# boot_cfg.net
KiCad netlist of a schematic drawn in Altium Designer
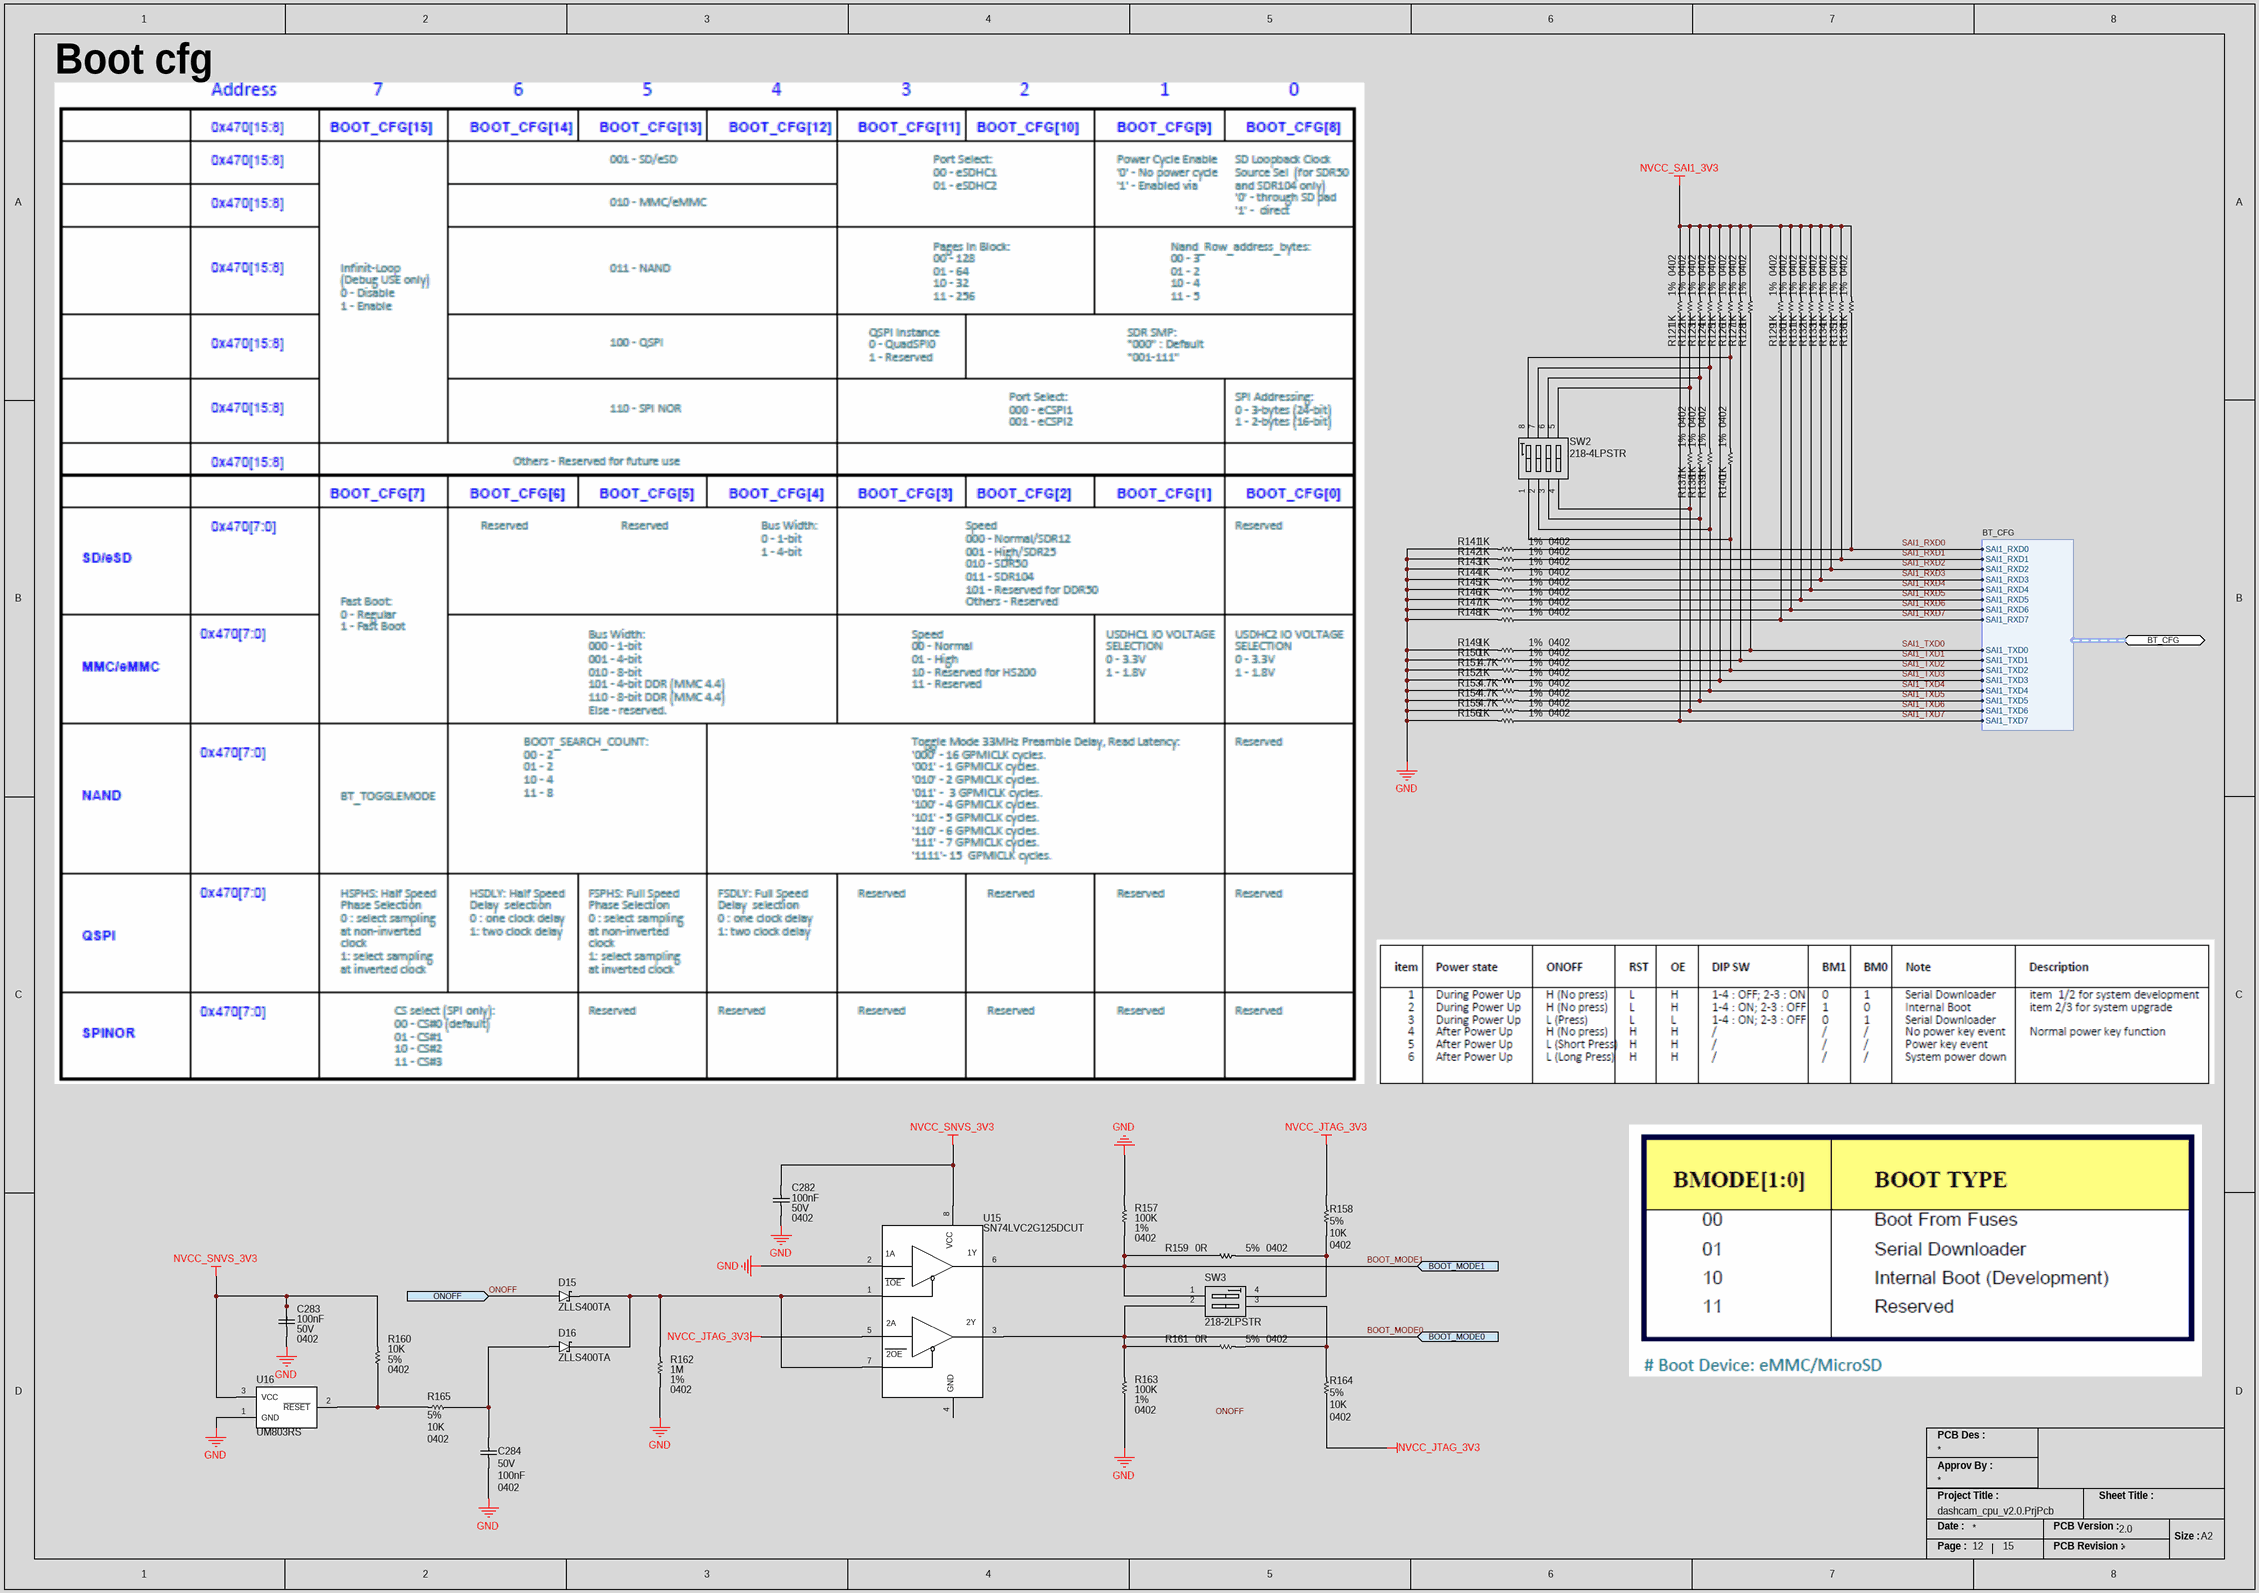
[diagram p0: boot_cfg.SchDoc]

(export (version "E")
  (design (tool "Eeschema 10.0.6"))
  (components
    (comp (ref "C282")
      (value "GRM155R71H104KE14D")
      (footprint "CAP_0402_CAPC1005X05N")
      (description "Multilayer Ceramic Capacitor, 0.1 uF, 16 V, ± 10%, X7R, 0402 [1005 Metric]")
      (fields
        (field (name "MANUFACTURER") "Murata")
        (field (name "TOLERANCE") "10%")
        (field (name "VOLTAGE RATING") "50V")
        (field (name "CAPACITANCE") "100nF")
        (field (name "CASE/PACKAGE") "0402")
      )
      (libsource (lib "Electronic Devices_LIB") (part "CAP_100NF_50V_X7R_0402"))
    )
    (comp (ref "C283")
      (value "GRM155R71H104KE14D")
      (footprint "CAP_0402_CAPC1005X05N")
      (description "Multilayer Ceramic Capacitor, 0.1 uF, 16 V, ± 10%, X7R, 0402 [1005 Metric]")
      (fields
        (field (name "MANUFACTURER") "Murata")
        (field (name "TOLERANCE") "10%")
        (field (name "VOLTAGE RATING") "50V")
        (field (name "CAPACITANCE") "100nF")
        (field (name "CASE/PACKAGE") "0402")
      )
      (libsource (lib "Electronic Devices_LIB") (part "CAP_100NF_50V_X7R_0402"))
    )
    (comp (ref "C284")
      (value "GRM155R71H104KE14D")
      (footprint "CAP_0402_CAPC1005X05N")
      (description "Multilayer Ceramic Capacitor, 0.1 uF, 16 V, ± 10%, X7R, 0402 [1005 Metric]")
      (fields
        (field (name "MANUFACTURER") "Murata")
        (field (name "TOLERANCE") "10%")
        (field (name "VOLTAGE RATING") "50V")
        (field (name "CAPACITANCE") "100nF")
        (field (name "CASE/PACKAGE") "0402")
      )
      (libsource (lib "Electronic Devices_LIB") (part "CAP_100NF_50V_X7R_0402"))
    )
    (comp (ref "D15")
      (value "ZLLS400TA")
      (footprint "DIO_SOD2512X113N")
      (description "DIODE SCHOTTKY 40V 520MA SOD323")
      (fields (field (name "MANUFACTURER") "Diodes Zetex"))
      (libsource (lib "Electronic Devices_LIB") (part "DIO_SCTKY_40V_520mA_ZLLS400TA"))
    )
    (comp (ref "D16")
      (value "ZLLS400TA")
      (footprint "DIO_SOD2512X113N")
      (description "DIODE SCHOTTKY 40V 520MA SOD323")
      (fields (field (name "MANUFACTURER") "Diodes Zetex"))
      (libsource (lib "Electronic Devices_LIB") (part "DIO_SCTKY_40V_520mA_ZLLS400TA"))
    )
    (comp (ref "R121")
      (value "ERJ-2RKF1001X")
      (footprint "RES_0402_RESC1005X04N")
      (description "RES SMD 1K OHM 1% 1/10W 0402")
      (fields
        (field (name "MANUFACTURER") "Panasonic")
        (field (name "RESISTANCE") "1K")
        (field (name "TOLERANCE") "1%")
        (field (name "CASE/PACKAGE") "0402")
      )
      (libsource (lib "Electronic Devices_LIB") (part "RES_1K_1%_100mW_0402"))
    )
    (comp (ref "R122")
      (value "ERJ-2RKF1001X")
      (footprint "RES_0402_RESC1005X04N")
      (description "RES SMD 1K OHM 1% 1/10W 0402")
      (fields
        (field (name "MANUFACTURER") "Panasonic")
        (field (name "RESISTANCE") "1K")
        (field (name "TOLERANCE") "1%")
        (field (name "CASE/PACKAGE") "0402")
      )
      (libsource (lib "Electronic Devices_LIB") (part "RES_1K_1%_100mW_0402"))
    )
    (comp (ref "R123")
      (value "ERJ-2RKF1001X")
      (footprint "RES_0402_RESC1005X04N")
      (description "RES SMD 1K OHM 1% 1/10W 0402")
      (fields
        (field (name "MANUFACTURER") "Panasonic")
        (field (name "RESISTANCE") "1K")
        (field (name "TOLERANCE") "1%")
        (field (name "CASE/PACKAGE") "0402")
      )
      (libsource (lib "Electronic Devices_LIB") (part "RES_1K_1%_100mW_0402"))
    )
    (comp (ref "R124")
      (value "ERJ-2RKF1001X")
      (footprint "RES_0402_RESC1005X04N")
      (description "RES SMD 1K OHM 1% 1/10W 0402")
      (fields
        (field (name "MANUFACTURER") "Panasonic")
        (field (name "RESISTANCE") "1K")
        (field (name "TOLERANCE") "1%")
        (field (name "CASE/PACKAGE") "0402")
      )
      (libsource (lib "Electronic Devices_LIB") (part "RES_1K_1%_100mW_0402"))
    )
    (comp (ref "R125")
      (value "ERJ-2RKF1001X")
      (footprint "RES_0402_RESC1005X04N")
      (description "RES SMD 1K OHM 1% 1/10W 0402")
      (fields
        (field (name "MANUFACTURER") "Panasonic")
        (field (name "RESISTANCE") "1K")
        (field (name "TOLERANCE") "1%")
        (field (name "CASE/PACKAGE") "0402")
      )
      (libsource (lib "Electronic Devices_LIB") (part "RES_1K_1%_100mW_0402"))
    )
    (comp (ref "R126")
      (value "ERJ-2RKF1001X")
      (footprint "RES_0402_RESC1005X04N")
      (description "RES SMD 1K OHM 1% 1/10W 0402")
      (fields
        (field (name "MANUFACTURER") "Panasonic")
        (field (name "RESISTANCE") "1K")
        (field (name "TOLERANCE") "1%")
        (field (name "CASE/PACKAGE") "0402")
      )
      (libsource (lib "Electronic Devices_LIB") (part "RES_1K_1%_100mW_0402"))
    )
    (comp (ref "R127")
      (value "ERJ-2RKF1001X")
      (footprint "RES_0402_RESC1005X04N")
      (description "RES SMD 1K OHM 1% 1/10W 0402")
      (fields
        (field (name "MANUFACTURER") "Panasonic")
        (field (name "RESISTANCE") "1K")
        (field (name "TOLERANCE") "1%")
        (field (name "CASE/PACKAGE") "0402")
      )
      (libsource (lib "Electronic Devices_LIB") (part "RES_1K_1%_100mW_0402"))
    )
    (comp (ref "R128")
      (value "ERJ-2RKF1001X")
      (footprint "RES_0402_RESC1005X04N")
      (description "RES SMD 1K OHM 1% 1/10W 0402")
      (fields
        (field (name "MANUFACTURER") "Panasonic")
        (field (name "RESISTANCE") "1K")
        (field (name "TOLERANCE") "1%")
        (field (name "CASE/PACKAGE") "0402")
      )
      (libsource (lib "Electronic Devices_LIB") (part "RES_1K_1%_100mW_0402"))
    )
    (comp (ref "R129")
      (value "ERJ-2RKF1001X")
      (footprint "RES_0402_RESC1005X04N")
      (description "RES SMD 1K OHM 1% 1/10W 0402")
      (fields
        (field (name "MANUFACTURER") "Panasonic")
        (field (name "RESISTANCE") "1K")
        (field (name "TOLERANCE") "1%")
        (field (name "CASE/PACKAGE") "0402")
      )
      (libsource (lib "Electronic Devices_LIB") (part "RES_1K_1%_100mW_0402"))
    )
    (comp (ref "R130")
      (value "ERJ-2RKF1001X")
      (footprint "RES_0402_RESC1005X04N")
      (description "RES SMD 1K OHM 1% 1/10W 0402")
      (fields
        (field (name "MANUFACTURER") "Panasonic")
        (field (name "RESISTANCE") "1K")
        (field (name "TOLERANCE") "1%")
        (field (name "CASE/PACKAGE") "0402")
      )
      (libsource (lib "Electronic Devices_LIB") (part "RES_1K_1%_100mW_0402"))
    )
    (comp (ref "R131")
      (value "ERJ-2RKF1001X")
      (footprint "RES_0402_RESC1005X04N")
      (description "RES SMD 1K OHM 1% 1/10W 0402")
      (fields
        (field (name "MANUFACTURER") "Panasonic")
        (field (name "RESISTANCE") "1K")
        (field (name "TOLERANCE") "1%")
        (field (name "CASE/PACKAGE") "0402")
      )
      (libsource (lib "Electronic Devices_LIB") (part "RES_1K_1%_100mW_0402"))
    )
    (comp (ref "R132")
      (value "ERJ-2RKF1001X")
      (footprint "RES_0402_RESC1005X04N")
      (description "RES SMD 1K OHM 1% 1/10W 0402")
      (fields
        (field (name "MANUFACTURER") "Panasonic")
        (field (name "RESISTANCE") "1K")
        (field (name "TOLERANCE") "1%")
        (field (name "CASE/PACKAGE") "0402")
      )
      (libsource (lib "Electronic Devices_LIB") (part "RES_1K_1%_100mW_0402"))
    )
    (comp (ref "R133")
      (value "ERJ-2RKF1001X")
      (footprint "RES_0402_RESC1005X04N")
      (description "RES SMD 1K OHM 1% 1/10W 0402")
      (fields
        (field (name "MANUFACTURER") "Panasonic")
        (field (name "RESISTANCE") "1K")
        (field (name "TOLERANCE") "1%")
        (field (name "CASE/PACKAGE") "0402")
      )
      (libsource (lib "Electronic Devices_LIB") (part "RES_1K_1%_100mW_0402"))
    )
    (comp (ref "R134")
      (value "ERJ-2RKF1001X")
      (footprint "RES_0402_RESC1005X04N")
      (description "RES SMD 1K OHM 1% 1/10W 0402")
      (fields
        (field (name "MANUFACTURER") "Panasonic")
        (field (name "RESISTANCE") "1K")
        (field (name "TOLERANCE") "1%")
        (field (name "CASE/PACKAGE") "0402")
      )
      (libsource (lib "Electronic Devices_LIB") (part "RES_1K_1%_100mW_0402"))
    )
    (comp (ref "R135")
      (value "ERJ-2RKF1001X")
      (footprint "RES_0402_RESC1005X04N")
      (description "RES SMD 1K OHM 1% 1/10W 0402")
      (fields
        (field (name "MANUFACTURER") "Panasonic")
        (field (name "RESISTANCE") "1K")
        (field (name "TOLERANCE") "1%")
        (field (name "CASE/PACKAGE") "0402")
      )
      (libsource (lib "Electronic Devices_LIB") (part "RES_1K_1%_100mW_0402"))
    )
    (comp (ref "R136")
      (value "ERJ-2RKF1001X")
      (footprint "RES_0402_RESC1005X04N")
      (description "RES SMD 1K OHM 1% 1/10W 0402")
      (fields
        (field (name "MANUFACTURER") "Panasonic")
        (field (name "RESISTANCE") "1K")
        (field (name "TOLERANCE") "1%")
        (field (name "CASE/PACKAGE") "0402")
      )
      (libsource (lib "Electronic Devices_LIB") (part "RES_1K_1%_100mW_0402"))
    )
    (comp (ref "R137")
      (value "ERJ-2RKF1001X")
      (footprint "RES_0402_RESC1005X04N")
      (description "RES SMD 1K OHM 1% 1/10W 0402")
      (fields
        (field (name "MANUFACTURER") "Panasonic")
        (field (name "RESISTANCE") "1K")
        (field (name "TOLERANCE") "1%")
        (field (name "CASE/PACKAGE") "0402")
      )
      (libsource (lib "Electronic Devices_LIB") (part "RES_1K_1%_100mW_0402"))
    )
    (comp (ref "R138")
      (value "ERJ-2RKF1001X")
      (footprint "RES_0402_RESC1005X04N")
      (description "RES SMD 1K OHM 1% 1/10W 0402")
      (fields
        (field (name "MANUFACTURER") "Panasonic")
        (field (name "RESISTANCE") "1K")
        (field (name "TOLERANCE") "1%")
        (field (name "CASE/PACKAGE") "0402")
      )
      (libsource (lib "Electronic Devices_LIB") (part "RES_1K_1%_100mW_0402"))
    )
    (comp (ref "R139")
      (value "ERJ-2RKF1001X")
      (footprint "RES_0402_RESC1005X04N")
      (description "RES SMD 1K OHM 1% 1/10W 0402")
      (fields
        (field (name "MANUFACTURER") "Panasonic")
        (field (name "RESISTANCE") "1K")
        (field (name "TOLERANCE") "1%")
        (field (name "CASE/PACKAGE") "0402")
      )
      (libsource (lib "Electronic Devices_LIB") (part "RES_1K_1%_100mW_0402"))
    )
    (comp (ref "R140")
      (value "ERJ-2RKF1001X")
      (footprint "RES_0402_RESC1005X04N")
      (description "RES SMD 1K OHM 1% 1/10W 0402")
      (fields
        (field (name "MANUFACTURER") "Panasonic")
        (field (name "RESISTANCE") "1K")
        (field (name "TOLERANCE") "1%")
        (field (name "CASE/PACKAGE") "0402")
      )
      (libsource (lib "Electronic Devices_LIB") (part "RES_1K_1%_100mW_0402"))
    )
    (comp (ref "R141")
      (value "ERJ-2RKF1001X")
      (footprint "RES_0402_RESC1005X04N")
      (description "RES SMD 1K OHM 1% 1/10W 0402")
      (fields
        (field (name "MANUFACTURER") "Panasonic")
        (field (name "RESISTANCE") "1K")
        (field (name "TOLERANCE") "1%")
        (field (name "CASE/PACKAGE") "0402")
      )
      (libsource (lib "Electronic Devices_LIB") (part "RES_1K_1%_100mW_0402"))
    )
    (comp (ref "R142")
      (value "ERJ-2RKF1001X")
      (footprint "RES_0402_RESC1005X04N")
      (description "RES SMD 1K OHM 1% 1/10W 0402")
      (fields
        (field (name "MANUFACTURER") "Panasonic")
        (field (name "RESISTANCE") "1K")
        (field (name "TOLERANCE") "1%")
        (field (name "CASE/PACKAGE") "0402")
      )
      (libsource (lib "Electronic Devices_LIB") (part "RES_1K_1%_100mW_0402"))
    )
    (comp (ref "R143")
      (value "ERJ-2RKF1001X")
      (footprint "RES_0402_RESC1005X04N")
      (description "RES SMD 1K OHM 1% 1/10W 0402")
      (fields
        (field (name "MANUFACTURER") "Panasonic")
        (field (name "RESISTANCE") "1K")
        (field (name "TOLERANCE") "1%")
        (field (name "CASE/PACKAGE") "0402")
      )
      (libsource (lib "Electronic Devices_LIB") (part "RES_1K_1%_100mW_0402"))
    )
    (comp (ref "R144")
      (value "ERJ-2RKF1001X")
      (footprint "RES_0402_RESC1005X04N")
      (description "RES SMD 1K OHM 1% 1/10W 0402")
      (fields
        (field (name "MANUFACTURER") "Panasonic")
        (field (name "RESISTANCE") "1K")
        (field (name "TOLERANCE") "1%")
        (field (name "CASE/PACKAGE") "0402")
      )
      (libsource (lib "Electronic Devices_LIB") (part "RES_1K_1%_100mW_0402"))
    )
    (comp (ref "R145")
      (value "ERJ-2RKF1001X")
      (footprint "RES_0402_RESC1005X04N")
      (description "RES SMD 1K OHM 1% 1/10W 0402")
      (fields
        (field (name "MANUFACTURER") "Panasonic")
        (field (name "RESISTANCE") "1K")
        (field (name "TOLERANCE") "1%")
        (field (name "CASE/PACKAGE") "0402")
      )
      (libsource (lib "Electronic Devices_LIB") (part "RES_1K_1%_100mW_0402"))
    )
    (comp (ref "R146")
      (value "ERJ-2RKF1001X")
      (footprint "RES_0402_RESC1005X04N")
      (description "RES SMD 1K OHM 1% 1/10W 0402")
      (fields
        (field (name "MANUFACTURER") "Panasonic")
        (field (name "RESISTANCE") "1K")
        (field (name "TOLERANCE") "1%")
        (field (name "CASE/PACKAGE") "0402")
      )
      (libsource (lib "Electronic Devices_LIB") (part "RES_1K_1%_100mW_0402"))
    )
    (comp (ref "R147")
      (value "ERJ-2RKF1001X")
      (footprint "RES_0402_RESC1005X04N")
      (description "RES SMD 1K OHM 1% 1/10W 0402")
      (fields
        (field (name "MANUFACTURER") "Panasonic")
        (field (name "RESISTANCE") "1K")
        (field (name "TOLERANCE") "1%")
        (field (name "CASE/PACKAGE") "0402")
      )
      (libsource (lib "Electronic Devices_LIB") (part "RES_1K_1%_100mW_0402"))
    )
    (comp (ref "R148")
      (value "ERJ-2RKF1001X")
      (footprint "RES_0402_RESC1005X04N")
      (description "RES SMD 1K OHM 1% 1/10W 0402")
      (fields
        (field (name "MANUFACTURER") "Panasonic")
        (field (name "RESISTANCE") "1K")
        (field (name "TOLERANCE") "1%")
        (field (name "CASE/PACKAGE") "0402")
      )
      (libsource (lib "Electronic Devices_LIB") (part "RES_1K_1%_100mW_0402"))
    )
    (comp (ref "R149")
      (value "ERJ-2RKF1001X")
      (footprint "RES_0402_RESC1005X04N")
      (description "RES SMD 1K OHM 1% 1/10W 0402")
      (fields
        (field (name "MANUFACTURER") "Panasonic")
        (field (name "RESISTANCE") "1K")
        (field (name "TOLERANCE") "1%")
        (field (name "CASE/PACKAGE") "0402")
      )
      (libsource (lib "Electronic Devices_LIB") (part "RES_1K_1%_100mW_0402"))
    )
    (comp (ref "R150")
      (value "ERJ-2RKF1001X")
      (footprint "RES_0402_RESC1005X04N")
      (description "RES SMD 1K OHM 1% 1/10W 0402")
      (fields
        (field (name "MANUFACTURER") "Panasonic")
        (field (name "RESISTANCE") "1K")
        (field (name "TOLERANCE") "1%")
        (field (name "CASE/PACKAGE") "0402")
      )
      (libsource (lib "Electronic Devices_LIB") (part "RES_1K_1%_100mW_0402"))
    )
    (comp (ref "R151")
      (value "ERJ-2RKF4701X")
      (footprint "RES_0402_RESC1005X04N")
      (description "Res Thick Film 0402 4.7K Ohm 1% 0.1W ±100ppm/°C Molded SMD Punched Carrier T/R")
      (fields
        (field (name "MANUFACTURER") "Panasonic")
        (field (name "TOLERANCE") "1%")
        (field (name "CASE CODE (IMPERIAL)") "0402")
        (field (name "RESISTANCE") "4.7K")
      )
      (libsource (lib "Electronic Devices_LIB") (part "RES_4.7K_1%_100mW_0402"))
    )
    (comp (ref "R152")
      (value "ERJ-2RKF1001X")
      (footprint "RES_0402_RESC1005X04N")
      (description "RES SMD 1K OHM 1% 1/10W 0402")
      (fields
        (field (name "MANUFACTURER") "Panasonic")
        (field (name "RESISTANCE") "1K")
        (field (name "TOLERANCE") "1%")
        (field (name "CASE/PACKAGE") "0402")
      )
      (libsource (lib "Electronic Devices_LIB") (part "RES_1K_1%_100mW_0402"))
    )
    (comp (ref "R153")
      (value "ERJ-2RKF4701X")
      (footprint "RES_0402_RESC1005X04N")
      (description "Res Thick Film 0402 4.7K Ohm 1% 0.1W ±100ppm/°C Molded SMD Punched Carrier T/R")
      (fields
        (field (name "MANUFACTURER") "Panasonic")
        (field (name "TOLERANCE") "1%")
        (field (name "CASE CODE (IMPERIAL)") "0402")
        (field (name "RESISTANCE") "4.7K")
      )
      (libsource (lib "Electronic Devices_LIB") (part "RES_4.7K_1%_100mW_0402"))
    )
    (comp (ref "R154")
      (value "ERJ-2RKF4701X")
      (footprint "RES_0402_RESC1005X04N")
      (description "Res Thick Film 0402 4.7K Ohm 1% 0.1W ±100ppm/°C Molded SMD Punched Carrier T/R")
      (fields
        (field (name "MANUFACTURER") "Panasonic")
        (field (name "TOLERANCE") "1%")
        (field (name "CASE CODE (IMPERIAL)") "0402")
        (field (name "RESISTANCE") "4.7K")
      )
      (libsource (lib "Electronic Devices_LIB") (part "RES_4.7K_1%_100mW_0402"))
    )
    (comp (ref "R155")
      (value "ERJ-2RKF4701X")
      (footprint "RES_0402_RESC1005X04N")
      (description "Res Thick Film 0402 4.7K Ohm 1% 0.1W ±100ppm/°C Molded SMD Punched Carrier T/R")
      (fields
        (field (name "MANUFACTURER") "Panasonic")
        (field (name "TOLERANCE") "1%")
        (field (name "CASE CODE (IMPERIAL)") "0402")
        (field (name "RESISTANCE") "4.7K")
      )
      (libsource (lib "Electronic Devices_LIB") (part "RES_4.7K_1%_100mW_0402"))
    )
    (comp (ref "R156")
      (value "ERJ-2RKF1001X")
      (footprint "RES_0402_RESC1005X04N")
      (description "RES SMD 1K OHM 1% 1/10W 0402")
      (fields
        (field (name "MANUFACTURER") "Panasonic")
        (field (name "RESISTANCE") "1K")
        (field (name "TOLERANCE") "1%")
        (field (name "CASE/PACKAGE") "0402")
      )
      (libsource (lib "Electronic Devices_LIB") (part "RES_1K_1%_100mW_0402"))
    )
    (comp (ref "R157")
      (value "RC0402FR-07100KL")
      (footprint "RES_0402_RESC1005X04N")
      (description "SMD Chip Resistor, 100 kOhm, ± 1%, 63 mW, 0402 [1005 Metric], Thick Film, General Purpose")
      (fields
        (field (name "MANUFACTURER") "Yageo")
        (field (name "RESISTANCE") "100K")
        (field (name "TOLERANCE") "1%")
        (field (name "CASE/PACKAGE") "0402")
      )
      (libsource (lib "Electronic Devices_LIB") (part "RES_100K_1%_100mW_0402"))
    )
    (comp (ref "R158")
      (value "ERJ-2GEJ103X")
      (footprint "RES_0402_RESC1005X04N")
      (description "Res Thick Film 0402 10K Ohm 5% 1/10W ±200ppm/°C Molded SMD Punched Carrier T/R")
      (fields
        (field (name "MANUFACTURER") "Panasonic")
        (field (name "TOLERANCE") "5%")
        (field (name "RESISTANCE") "10K")
        (field (name "CASE/PACKAGE") "0402")
      )
      (libsource (lib "Electronic Devices_LIB") (part "RES_10K_5%_100mW_0402"))
    )
    (comp (ref "R159")
      (value "ERJ-2GE0R00X")
      (footprint "RES_0402_RESC1005X04N")
      (description "SMD Chip Resistor, Jumper, 0 ohm, 100 mW, 0402 [1005 Metric], Thick Film, General Purpose")
      (fields
        (field (name "MANUFACTURER") "Panasonic")
        (field (name "CASE CODE (IMPERIAL)") "0402")
        (field (name "TOLERANCE") "5%")
        (field (name "RESISTANCE") "0R")
      )
      (libsource (lib "Electronic Devices_LIB") (part "RES_0R_5%_100mW_0402"))
    )
    (comp (ref "R160")
      (value "ERJ-2GEJ103X")
      (footprint "RES_0402_RESC1005X04N")
      (description "Res Thick Film 0402 10K Ohm 5% 1/10W ±200ppm/°C Molded SMD Punched Carrier T/R")
      (fields
        (field (name "MANUFACTURER") "Panasonic")
        (field (name "TOLERANCE") "5%")
        (field (name "RESISTANCE") "10K")
        (field (name "CASE/PACKAGE") "0402")
      )
      (libsource (lib "Electronic Devices_LIB") (part "RES_10K_5%_100mW_0402"))
    )
    (comp (ref "R161")
      (value "ERJ-2GE0R00X")
      (footprint "RES_0402_RESC1005X04N")
      (description "SMD Chip Resistor, Jumper, 0 ohm, 100 mW, 0402 [1005 Metric], Thick Film, General Purpose")
      (fields
        (field (name "MANUFACTURER") "Panasonic")
        (field (name "CASE CODE (IMPERIAL)") "0402")
        (field (name "TOLERANCE") "5%")
        (field (name "RESISTANCE") "0R")
      )
      (libsource (lib "Electronic Devices_LIB") (part "RES_0R_5%_100mW_0402"))
    )
    (comp (ref "R162")
      (value "CR0402-FX-1004GLF")
      (footprint "RES_0402_RESC1005X04N")
      (description "Res Thick Film 0402 1M Ohm 1% 1/16W ±100ppm/°C Molded SMD SMD Paper Tape on Plastic Reel")
      (fields
        (field (name "MANUFACTURER") "Bourns")
        (field (name "RESISTANCE") "1M")
        (field (name "TOLERANCE") "1%")
        (field (name "CASE/PACKAGE") "0402")
      )
      (libsource (lib "Electronic Devices_LIB") (part "RES_1M_1%_63mW_0402"))
    )
    (comp (ref "R163")
      (value "RC0402FR-07100KL")
      (footprint "RES_0402_RESC1005X04N")
      (description "SMD Chip Resistor, 100 kOhm, ± 1%, 63 mW, 0402 [1005 Metric], Thick Film, General Purpose")
      (fields
        (field (name "MANUFACTURER") "Yageo")
        (field (name "RESISTANCE") "100K")
        (field (name "TOLERANCE") "1%")
        (field (name "CASE/PACKAGE") "0402")
      )
      (libsource (lib "Electronic Devices_LIB") (part "RES_100K_1%_100mW_0402"))
    )
    (comp (ref "R164")
      (value "ERJ-2GEJ103X")
      (footprint "RES_0402_RESC1005X04N")
      (description "Res Thick Film 0402 10K Ohm 5% 1/10W ±200ppm/°C Molded SMD Punched Carrier T/R")
      (fields
        (field (name "MANUFACTURER") "Panasonic")
        (field (name "TOLERANCE") "5%")
        (field (name "RESISTANCE") "10K")
        (field (name "CASE/PACKAGE") "0402")
      )
      (libsource (lib "Electronic Devices_LIB") (part "RES_10K_5%_100mW_0402"))
    )
    (comp (ref "R165")
      (value "ERJ-2GEJ103X")
      (footprint "RES_0402_RESC1005X04N")
      (description "Res Thick Film 0402 10K Ohm 5% 1/10W ±200ppm/°C Molded SMD Punched Carrier T/R")
      (fields
        (field (name "MANUFACTURER") "Panasonic")
        (field (name "TOLERANCE") "5%")
        (field (name "RESISTANCE") "10K")
        (field (name "CASE/PACKAGE") "0402")
      )
      (libsource (lib "Electronic Devices_LIB") (part "RES_10K_5%_100mW_0402"))
    )
    (comp (ref "SW2")
      (value "218-4LPSTR")
      (footprint "SW_DIP_SOIC127P844X265-8N")
      (description "Switch DIP ON OFF SPST 4 Recessed Slide 0.025A 24VDC Gull Wing 1000Cycles 1.27mm SMD T/R")
      (fields (field (name "MANUFACTURER") "CTS"))
      (libsource (lib "Electronic Devices_LIB") (part "SWITCH_DIP_4P_25mA_218-4LPSTR"))
    )
    (comp (ref "SW3")
      (value "218-2LPSTR")
      (footprint "SW_DIP_2P_2182LPSTR")
      (description "Switch DIP ON OFF SPST 2 Recessed Slide 0.025A 24VDC Gull Wing 1000Cycles 1.27mm SMD T/R")
      (fields (field (name "MANUFACTURER") "CTS"))
      (libsource (lib "Electronic Devices_LIB") (part "SWITCH_DIP_2P_25mA_218-2LPSTR"))
    )
    (comp (ref "U15")
      (value "SN74LVC2G125DCUT")
      (footprint "IC_BUFF_SOP50P310X90-8N")
      (description "Buffer/Line Driver 2-CH Non-Inverting 3-ST CMOS 8-Pin VSSOP T/R")
      (fields (field (name "MANUFACTURER") "Texas Instruments"))
      (libsource (lib "Electronic Devices_LIB") (part "IC_BUFFER_2CH_SN74LVC2G125DCUT"))
    )
    (comp (ref "U16")
      (value "UM803RS")
      (footprint "IC_SUP_VOL_UM805RS")
      (description "3-Pin Microprocessor Reset Circuits")
      (fields (field (name "MANUFACTURER") "Union Semiconductor"))
      (libsource (lib "Electronic Devices_LIB") (part "IC_VOLTAGE_SUPERVISOR_UM803RS"))
    )
  )
  (nets
    (net (code "2") (name "/BOOT_MODE0") (class "Default")
      (node (ref "R161") (pin "1") (pinfunction "1_1") (pintype "passive"))
      (node (ref "R163") (pin "2") (pinfunction "2_2") (pintype "passive"))
      (node (ref "SW3") (pin "2") (pinfunction "A2_2") (pintype "passive"))
      (node (ref "U15") (pin "3") (pinfunction "2Y_3") (pintype "passive"))
    )
    (net (code "3") (name "/BOOT_MODE1") (class "Default")
      (node (ref "R157") (pin "1") (pinfunction "1_1") (pintype "passive"))
      (node (ref "R159") (pin "1") (pinfunction "1_1") (pintype "passive"))
      (node (ref "SW3") (pin "1") (pinfunction "A1_1") (pintype "passive"))
      (node (ref "U15") (pin "6") (pinfunction "1Y_6") (pintype "passive"))
    )
    (net (code "4") (name "/ONOFF") (class "Default")
      (node (ref "D15") (pin "2") (pinfunction "A_2") (pintype "passive"))
    )
    (net (code "5") (name "/SAI1_RXD0") (class "Default")
      (node (ref "R136") (pin "1") (pinfunction "1_1") (pintype "passive"))
      (node (ref "R141") (pin "1") (pinfunction "1_1") (pintype "passive"))
    )
    (net (code "6") (name "/SAI1_RXD1") (class "Default")
      (node (ref "R135") (pin "1") (pinfunction "1_1") (pintype "passive"))
      (node (ref "R142") (pin "1") (pinfunction "1_1") (pintype "passive"))
    )
    (net (code "7") (name "/SAI1_RXD2") (class "Default")
      (node (ref "R134") (pin "1") (pinfunction "1_1") (pintype "passive"))
      (node (ref "R143") (pin "1") (pinfunction "1_1") (pintype "passive"))
    )
    (net (code "8") (name "/SAI1_RXD3") (class "Default")
      (node (ref "R133") (pin "1") (pinfunction "1_1") (pintype "passive"))
      (node (ref "R144") (pin "1") (pinfunction "1_1") (pintype "passive"))
    )
    (net (code "9") (name "/SAI1_RXD4") (class "Default")
      (node (ref "R132") (pin "1") (pinfunction "1_1") (pintype "passive"))
      (node (ref "R145") (pin "1") (pinfunction "1_1") (pintype "passive"))
    )
    (net (code "10") (name "/SAI1_RXD5") (class "Default")
      (node (ref "R131") (pin "1") (pinfunction "1_1") (pintype "passive"))
      (node (ref "R146") (pin "1") (pinfunction "1_1") (pintype "passive"))
    )
    (net (code "11") (name "/SAI1_RXD6") (class "Default")
      (node (ref "R130") (pin "1") (pinfunction "1_1") (pintype "passive"))
      (node (ref "R147") (pin "1") (pinfunction "1_1") (pintype "passive"))
    )
    (net (code "12") (name "/SAI1_RXD7") (class "Default")
      (node (ref "R129") (pin "1") (pinfunction "1_1") (pintype "passive"))
      (node (ref "R148") (pin "1") (pinfunction "1_1") (pintype "passive"))
    )
    (net (code "13") (name "/SAI1_TXD0") (class "Default")
      (node (ref "R128") (pin "1") (pinfunction "1_1") (pintype "passive"))
      (node (ref "R149") (pin "1") (pinfunction "1_1") (pintype "passive"))
    )
    (net (code "14") (name "/SAI1_TXD1") (class "Default")
      (node (ref "R127") (pin "1") (pinfunction "1_1") (pintype "passive"))
      (node (ref "R150") (pin "1") (pinfunction "1_1") (pintype "passive"))
    )
    (net (code "15") (name "/SAI1_TXD2") (class "Default")
      (node (ref "R140") (pin "1") (pinfunction "1_1") (pintype "passive"))
      (node (ref "R151") (pin "2") (pinfunction "2_2") (pintype "passive"))
      (node (ref "SW2") (pin "1") (pinfunction "A1_1") (pintype "passive"))
    )
    (net (code "16") (name "/SAI1_TXD3") (class "Default")
      (node (ref "R125") (pin "1") (pinfunction "1_1") (pintype "passive"))
      (node (ref "R152") (pin "1") (pinfunction "1_1") (pintype "passive"))
    )
    (net (code "17") (name "/SAI1_TXD4") (class "Default")
      (node (ref "R139") (pin "1") (pinfunction "1_1") (pintype "passive"))
      (node (ref "R153") (pin "2") (pinfunction "2_2") (pintype "passive"))
      (node (ref "SW2") (pin "2") (pinfunction "A2_2") (pintype "passive"))
    )
    (net (code "18") (name "/SAI1_TXD5") (class "Default")
      (node (ref "R138") (pin "1") (pinfunction "1_1") (pintype "passive"))
      (node (ref "R154") (pin "2") (pinfunction "2_2") (pintype "passive"))
      (node (ref "SW2") (pin "3") (pinfunction "A3_3") (pintype "passive"))
    )
    (net (code "19") (name "/SAI1_TXD6") (class "Default")
      (node (ref "R137") (pin "1") (pinfunction "1_1") (pintype "passive"))
      (node (ref "R155") (pin "2") (pinfunction "2_2") (pintype "passive"))
      (node (ref "SW2") (pin "4") (pinfunction "A4_4") (pintype "passive"))
    )
    (net (code "20") (name "/SAI1_TXD7") (class "Default")
      (node (ref "R121") (pin "1") (pinfunction "1_1") (pintype "passive"))
      (node (ref "R156") (pin "1") (pinfunction "1_1") (pintype "passive"))
    )
    (net (code "22") (name "GND") (class "Default")
      (node (ref "C282") (pin "1") (pinfunction "1_1") (pintype "passive"))
      (node (ref "C283") (pin "1") (pinfunction "1_1") (pintype "passive"))
      (node (ref "C284") (pin "1") (pinfunction "1_1") (pintype "passive"))
      (node (ref "R141") (pin "2") (pinfunction "2_2") (pintype "passive"))
      (node (ref "R142") (pin "2") (pinfunction "2_2") (pintype "passive"))
      (node (ref "R143") (pin "2") (pinfunction "2_2") (pintype "passive"))
      (node (ref "R144") (pin "2") (pinfunction "2_2") (pintype "passive"))
      (node (ref "R145") (pin "2") (pinfunction "2_2") (pintype "passive"))
      (node (ref "R146") (pin "2") (pinfunction "2_2") (pintype "passive"))
      (node (ref "R147") (pin "2") (pinfunction "2_2") (pintype "passive"))
      (node (ref "R148") (pin "2") (pinfunction "2_2") (pintype "passive"))
      (node (ref "R149") (pin "2") (pinfunction "2_2") (pintype "passive"))
      (node (ref "R150") (pin "2") (pinfunction "2_2") (pintype "passive"))
      (node (ref "R151") (pin "1") (pinfunction "1_1") (pintype "passive"))
      (node (ref "R152") (pin "2") (pinfunction "2_2") (pintype "passive"))
      (node (ref "R153") (pin "1") (pinfunction "1_1") (pintype "passive"))
      (node (ref "R154") (pin "1") (pinfunction "1_1") (pintype "passive"))
      (node (ref "R155") (pin "1") (pinfunction "1_1") (pintype "passive"))
      (node (ref "R156") (pin "2") (pinfunction "2_2") (pintype "passive"))
      (node (ref "R157") (pin "2") (pinfunction "2_2") (pintype "passive"))
      (node (ref "R162") (pin "1") (pinfunction "1_1") (pintype "passive"))
      (node (ref "R163") (pin "1") (pinfunction "1_1") (pintype "passive"))
      (node (ref "U15") (pin "2") (pinfunction "1A_2") (pintype "passive"))
      (node (ref "U16") (pin "1") (pinfunction "GND_1") (pintype "passive"))
    )
    (net (code "23") (name "NVCC_JTAG_3V3") (class "Default")
      (node (ref "R158") (pin "2") (pinfunction "2_2") (pintype "passive"))
      (node (ref "R164") (pin "1") (pinfunction "1_1") (pintype "passive"))
      (node (ref "U15") (pin "5") (pinfunction "2A_5") (pintype "passive"))
    )
    (net (code "24") (name "NVCC_SAI1_3V3") (class "Default")
      (node (ref "R121") (pin "2") (pinfunction "2_2") (pintype "passive"))
      (node (ref "R122") (pin "2") (pinfunction "2_2") (pintype "passive"))
      (node (ref "R123") (pin "2") (pinfunction "2_2") (pintype "passive"))
      (node (ref "R124") (pin "2") (pinfunction "2_2") (pintype "passive"))
      (node (ref "R125") (pin "2") (pinfunction "2_2") (pintype "passive"))
      (node (ref "R126") (pin "2") (pinfunction "2_2") (pintype "passive"))
      (node (ref "R127") (pin "2") (pinfunction "2_2") (pintype "passive"))
      (node (ref "R128") (pin "2") (pinfunction "2_2") (pintype "passive"))
      (node (ref "R129") (pin "2") (pinfunction "2_2") (pintype "passive"))
      (node (ref "R130") (pin "2") (pinfunction "2_2") (pintype "passive"))
      (node (ref "R131") (pin "2") (pinfunction "2_2") (pintype "passive"))
      (node (ref "R132") (pin "2") (pinfunction "2_2") (pintype "passive"))
      (node (ref "R133") (pin "2") (pinfunction "2_2") (pintype "passive"))
      (node (ref "R134") (pin "2") (pinfunction "2_2") (pintype "passive"))
      (node (ref "R135") (pin "2") (pinfunction "2_2") (pintype "passive"))
      (node (ref "R136") (pin "2") (pinfunction "2_2") (pintype "passive"))
    )
    (net (code "25") (name "NVCC_SNVS_3V3") (class "Default")
      (node (ref "C282") (pin "2") (pinfunction "2_2") (pintype "passive"))
      (node (ref "C283") (pin "2") (pinfunction "2_2") (pintype "passive"))
      (node (ref "R160") (pin "2") (pinfunction "2_2") (pintype "passive"))
      (node (ref "U15") (pin "8") (pinfunction "VCC_8") (pintype "passive"))
      (node (ref "U16") (pin "3") (pinfunction "VCC_3") (pintype "passive"))
    )
    (net (code "26") (name "Net-(D15-K)") (class "Default")
      (node (ref "D15") (pin "1") (pinfunction "K_1") (pintype "passive"))
      (node (ref "D16") (pin "1") (pinfunction "K_1") (pintype "passive"))
      (node (ref "R162") (pin "2") (pinfunction "2_2") (pintype "passive"))
      (node (ref "U15") (pin "1") (pinfunction "~{1OE}_1") (pintype "passive"))
      (node (ref "U15") (pin "7") (pinfunction "~{2OE}_7") (pintype "passive"))
    )
    (net (code "27") (name "Net-(D16-A)") (class "Default")
      (node (ref "C284") (pin "2") (pinfunction "2_2") (pintype "passive"))
      (node (ref "D16") (pin "2") (pinfunction "A_2") (pintype "passive"))
      (node (ref "R165") (pin "1") (pinfunction "1_1") (pintype "passive"))
    )
    (net (code "28") (name "Net-(SW2-B1)") (class "Default")
      (node (ref "R126") (pin "1") (pinfunction "1_1") (pintype "passive"))
      (node (ref "R140") (pin "2") (pinfunction "2_2") (pintype "passive"))
      (node (ref "SW2") (pin "8") (pinfunction "B1_8") (pintype "passive"))
    )
    (net (code "29") (name "Net-(SW2-B2)") (class "Default")
      (node (ref "R124") (pin "1") (pinfunction "1_1") (pintype "passive"))
      (node (ref "R139") (pin "2") (pinfunction "2_2") (pintype "passive"))
      (node (ref "SW2") (pin "7") (pinfunction "B2_7") (pintype "passive"))
    )
    (net (code "30") (name "Net-(SW2-B3)") (class "Default")
      (node (ref "R123") (pin "1") (pinfunction "1_1") (pintype "passive"))
      (node (ref "R138") (pin "2") (pinfunction "2_2") (pintype "passive"))
      (node (ref "SW2") (pin "6") (pinfunction "B3_6") (pintype "passive"))
    )
    (net (code "31") (name "Net-(SW2-B4)") (class "Default")
      (node (ref "R122") (pin "1") (pinfunction "1_1") (pintype "passive"))
      (node (ref "R137") (pin "2") (pinfunction "2_2") (pintype "passive"))
      (node (ref "SW2") (pin "5") (pinfunction "B4_5") (pintype "passive"))
    )
    (net (code "32") (name "Net-(SW3-B1)") (class "Default")
      (node (ref "R158") (pin "1") (pinfunction "1_1") (pintype "passive"))
      (node (ref "R159") (pin "2") (pinfunction "2_2") (pintype "passive"))
      (node (ref "SW3") (pin "4") (pinfunction "B1_4") (pintype "passive"))
    )
    (net (code "33") (name "Net-(SW3-B2)") (class "Default")
      (node (ref "R161") (pin "2") (pinfunction "2_2") (pintype "passive"))
      (node (ref "R164") (pin "2") (pinfunction "2_2") (pintype "passive"))
      (node (ref "SW3") (pin "3") (pinfunction "B2_3") (pintype "passive"))
    )
    (net (code "34") (name "Net-(U16-~{RESET})") (class "Default")
      (node (ref "R160") (pin "1") (pinfunction "1_1") (pintype "passive"))
      (node (ref "R165") (pin "2") (pinfunction "2_2") (pintype "passive"))
      (node (ref "U16") (pin "2") (pinfunction "~{RESET}_2") (pintype "passive"))
    )
    (net (code "35") (name "unconnected-(U15-GND-Pad4)") (class "Default")
      (node (ref "U15") (pin "4") (pinfunction "GND_4") (pintype "passive"))
    )
  )
)
